# srd-05vdc-sl-c_single.net
KiCad netlist of a schematic drawn in EAGLE
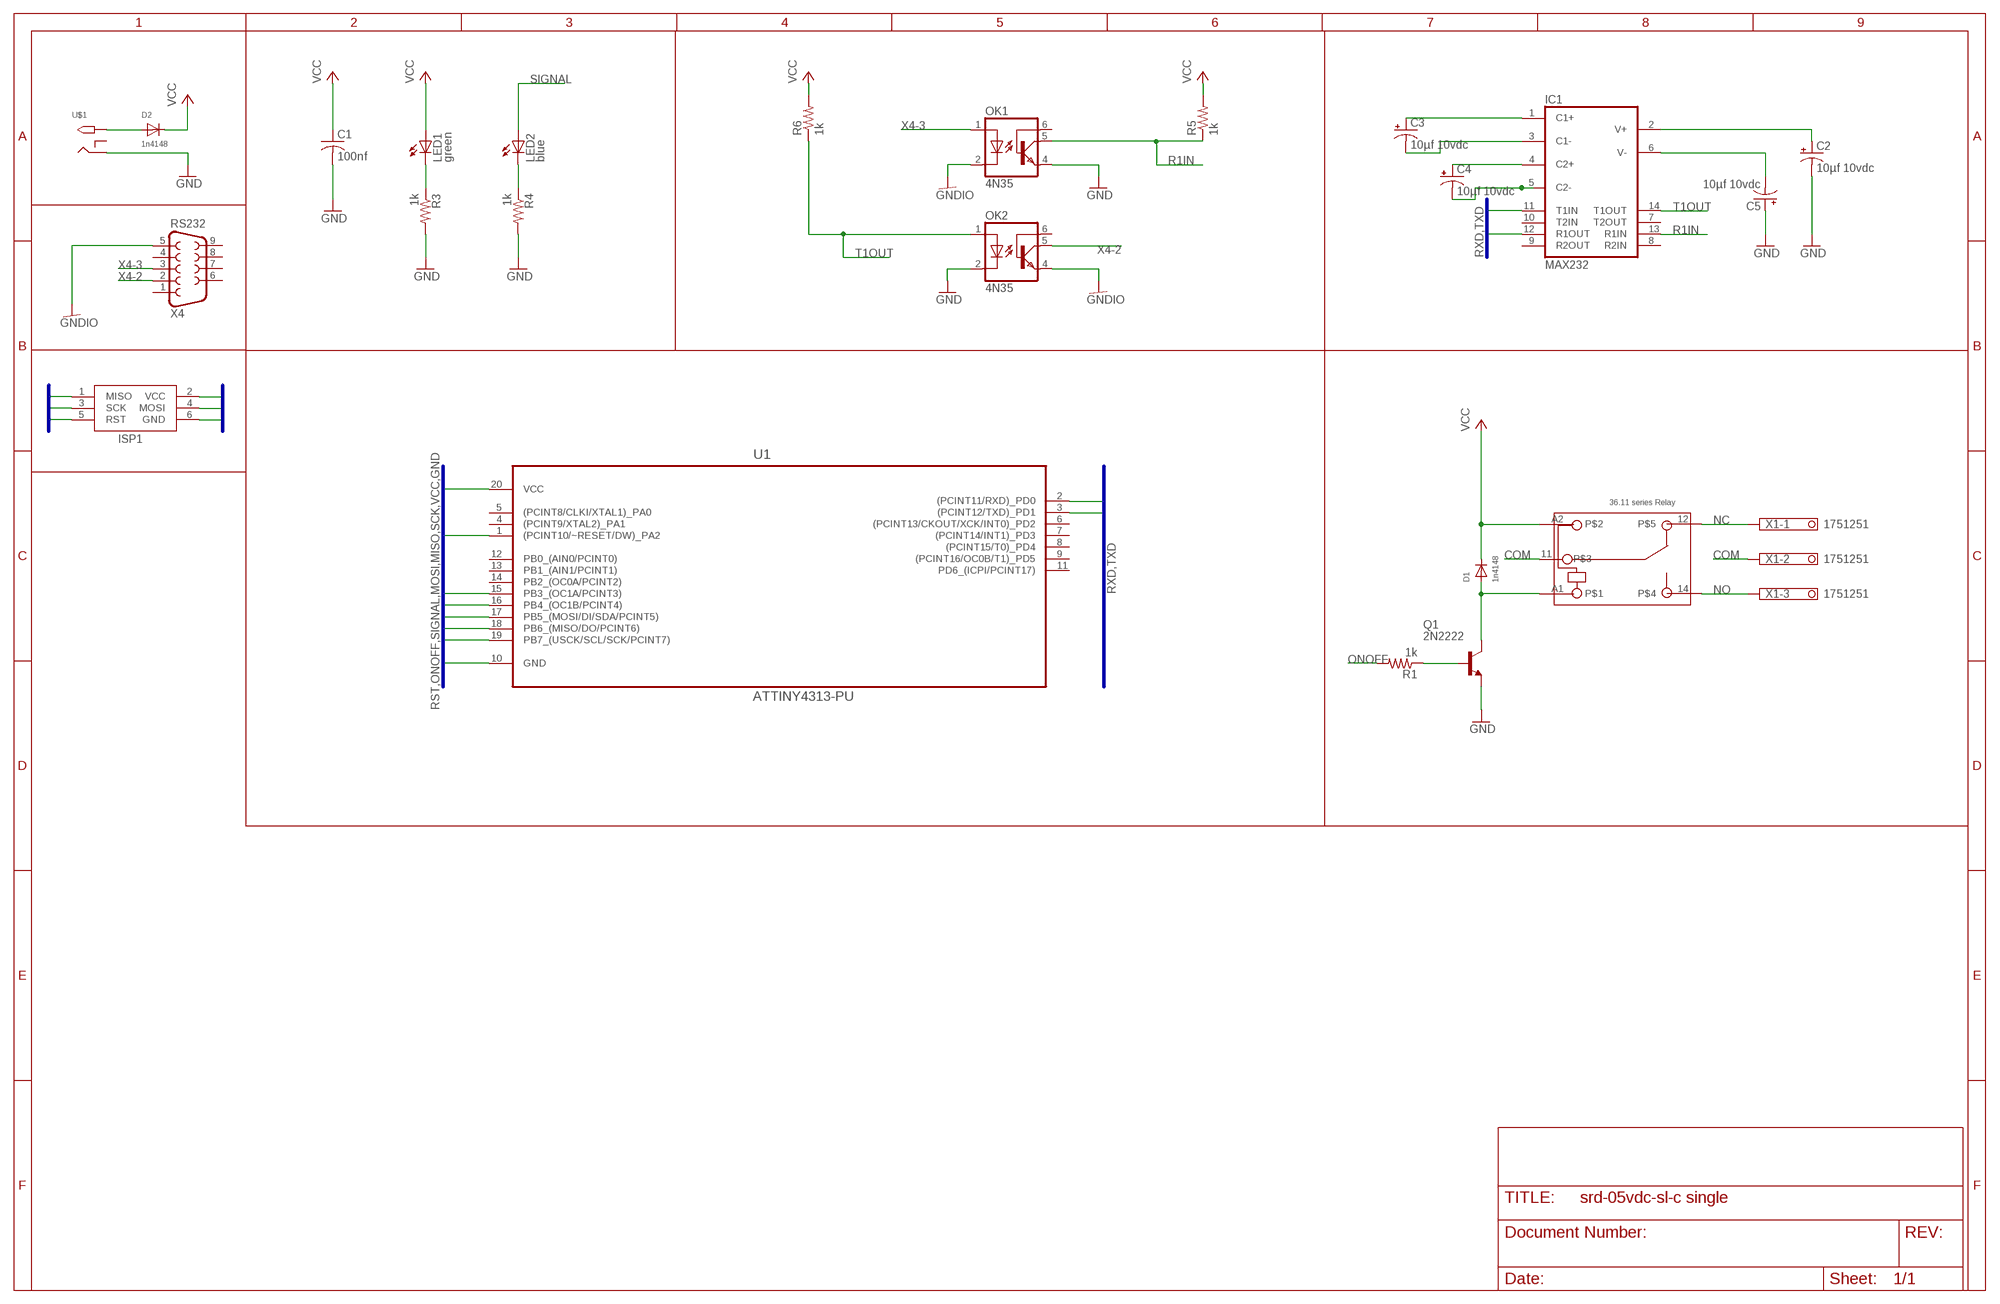
[diagram p0: schematic, sheet 1]

(export (version "E")
  (design (tool "Eeschema 10.0.6"))
  (components
    (comp (ref "C1")
      (value "100nf")
      (footprint "eagle-import:C025-025X050")
      (libsource (lib "eagle-import") (part "C-US025-025X050"))
    )
    (comp (ref "C2")
      (value "10µf 10vdc")
      (footprint "eagle-import:E2,5-6")
      (libsource (lib "eagle-import") (part "CPOL-USE2.5-6"))
    )
    (comp (ref "C3")
      (value "10µf 10vdc")
      (footprint "eagle-import:E2,5-6")
      (libsource (lib "eagle-import") (part "CPOL-USE2.5-6"))
    )
    (comp (ref "C4")
      (value "10µf 10vdc")
      (footprint "eagle-import:E2,5-6")
      (libsource (lib "eagle-import") (part "CPOL-USE2.5-6"))
    )
    (comp (ref "C5")
      (value "10µf 10vdc")
      (footprint "eagle-import:E2,5-6")
      (libsource (lib "eagle-import") (part "CPOL-USE2.5-6"))
    )
    (comp (ref "D1")
      (value "1n4148")
      (footprint "eagle-import:DO-1N4148")
      (libsource (lib "eagle-import") (part "DIODEDO-1N4148"))
    )
    (comp (ref "D2")
      (value "1n4148")
      (footprint "eagle-import:DO-1N4148")
      (libsource (lib "eagle-import") (part "DIODEDO-1N4148"))
    )
    (comp (ref "IC1")
      (value "MAX232")
      (footprint "eagle-import:DIL16")
      (fields (field (name "MF") "MAXIM") (field (name "MPN") "MAX232ACPE+"))
      (libsource (lib "eagle-import") (part "MAX232"))
    )
    (comp (ref "ISP1")
      (value "AVRISP-6")
      (footprint "eagle-import:AVRISP")
      (libsource (lib "eagle-import") (part "AVRISP-6"))
    )
    (comp (ref "LED1")
      (value "green")
      (footprint "eagle-import:LED3MM")
      (libsource (lib "eagle-import") (part "LED3MM"))
    )
    (comp (ref "LED2")
      (value "blue")
      (footprint "eagle-import:LED3MM")
      (libsource (lib "eagle-import") (part "LED3MM"))
    )
    (comp (ref "OK1")
      (value "4N35")
      (footprint "eagle-import:DIL06")
      (fields (field (name "MF") "FAIRCHILD SEMICONDUCTOR"))
      (libsource (lib "eagle-import") (part "4N35"))
    )
    (comp (ref "OK2")
      (value "4N35")
      (footprint "eagle-import:DIL06")
      (fields (field (name "MF") "FAIRCHILD SEMICONDUCTOR"))
      (libsource (lib "eagle-import") (part "4N35"))
    )
    (comp (ref "Q1")
      (value "2N2222")
      (footprint "eagle-import:TO92-EBC-OVAL")
      (libsource (lib "eagle-import") (part "2N2222"))
    )
    (comp (ref "R1")
      (value "1k")
      (footprint "eagle-import:0204_7")
      (libsource (lib "eagle-import") (part "R-US_0204/7"))
    )
    (comp (ref "R3")
      (value "1k")
      (footprint "eagle-import:0204_7")
      (libsource (lib "eagle-import") (part "R-US_0204/7"))
    )
    (comp (ref "R4")
      (value "1k")
      (footprint "eagle-import:0204_7")
      (libsource (lib "eagle-import") (part "R-US_0204/7"))
    )
    (comp (ref "R5")
      (value "1k")
      (footprint "eagle-import:0204_7")
      (libsource (lib "eagle-import") (part "R-US_0204/7"))
    )
    (comp (ref "R6")
      (value "1k")
      (footprint "eagle-import:0204_7")
      (libsource (lib "eagle-import") (part "R-US_0204/7"))
    )
    (comp (ref "SRD-05VDC-SL-C")
      (value "36.11")
      (footprint "eagle-import:36.11")
      (libsource (lib "eagle-import") (part "36.11"))
    )
    (comp (ref "U$1")
      (value "2.1MMJACKTHM")
      (footprint "eagle-import:PJ-102A")
      (libsource (lib "eagle-import") (part "2.1MMJACKTHM"))
    )
    (comp (ref "U1")
      (value "ATTINY4313-PU")
      (footprint "eagle-import:DIP254P762X533-20")
      (libsource (lib "eagle-import") (part "ATTINY4313-PU"))
    )
    (comp (ref "X1")
      (value "1751251")
      (footprint "eagle-import:1751251")
      (libsource (lib "eagle-import") (part "1751251"))
    )
    (comp (ref "X4")
      (value "RS232")
      (footprint "eagle-import:F09H")
      (libsource (lib "eagle-import") (part "F09H"))
    )
  )
  (nets
    (net (code "1") (name "/COM") (class "Default")
      (node (ref "SRD-05VDC-SL-C") (pin "11") (pinfunction "P$3_11") (pintype "passive"))
      (node (ref "X1") (pin "2") (pinfunction "K_2") (pintype "passive"))
    )
    (net (code "2") (name "/MISO") (class "Default")
      (node (ref "ISP1") (pin "1") (pinfunction "MISO_1") (pintype "input"))
      (node (ref "U1") (pin "18") (pinfunction "PB6_(MISO/DO/PCINT6)_18") (pintype "bidirectional"))
    )
    (net (code "3") (name "/MOSI") (class "Default")
      (node (ref "ISP1") (pin "4") (pinfunction "MOSI_4") (pintype "output"))
      (node (ref "U1") (pin "17") (pinfunction "PB5_(MOSI/DI/SDA/PCINT5)_17") (pintype "bidirectional"))
    )
    (net (code "4") (name "/NC") (class "Default")
      (node (ref "SRD-05VDC-SL-C") (pin "12") (pinfunction "P$5_12") (pintype "passive"))
      (node (ref "X1") (pin "1") (pinfunction "K_1") (pintype "passive"))
    )
    (net (code "5") (name "/NO") (class "Default")
      (node (ref "SRD-05VDC-SL-C") (pin "14") (pinfunction "P$4_14") (pintype "passive"))
      (node (ref "X1") (pin "3") (pinfunction "K_3") (pintype "passive"))
    )
    (net (code "6") (name "/ONOFF") (class "Default")
      (node (ref "R1") (pin "2") (pinfunction "2_2") (pintype "passive"))
      (node (ref "U1") (pin "15") (pinfunction "PB3_(OC1A/PCINT3)_15") (pintype "power_in"))
    )
    (net (code "7") (name "/R1IN") (class "Default")
      (node (ref "IC1") (pin "13") (pinfunction "R1IN_13") (pintype "input"))
      (node (ref "OK1") (pin "5") (pinfunction "COL_5") (pintype "passive"))
      (node (ref "R5") (pin "1") (pinfunction "1_1") (pintype "passive"))
    )
    (net (code "8") (name "/RST") (class "Default")
      (node (ref "ISP1") (pin "5") (pinfunction "RST_5") (pintype "output"))
      (node (ref "U1") (pin "1") (pinfunction "(PCINT10/~{RESET/DW})_PA2_1") (pintype "bidirectional"))
    )
    (net (code "9") (name "/RXD") (class "Default")
      (node (ref "IC1") (pin "12") (pinfunction "R1OUT_12") (pintype "output"))
      (node (ref "U1") (pin "2") (pinfunction "(PCINT11/RXD)_PD0_2") (pintype "bidirectional"))
    )
    (net (code "10") (name "/SCK") (class "Default")
      (node (ref "ISP1") (pin "3") (pinfunction "SCK_3") (pintype "output"))
      (node (ref "U1") (pin "19") (pinfunction "PB7_(USCK/SCL/SCK/PCINT7)_19") (pintype "bidirectional"))
    )
    (net (code "11") (name "/SIGNAL") (class "Default")
      (node (ref "LED2") (pin "A") (pinfunction "A_A") (pintype "passive"))
      (node (ref "U1") (pin "16") (pinfunction "PB4_(OC1B/PCINT4)_16") (pintype "passive"))
    )
    (net (code "12") (name "/T1OUT") (class "Default")
      (node (ref "IC1") (pin "14") (pinfunction "T1OUT_14") (pintype "output"))
      (node (ref "OK2") (pin "1") (pinfunction "A_1") (pintype "passive"))
      (node (ref "R6") (pin "1") (pinfunction "1_1") (pintype "passive"))
    )
    (net (code "13") (name "/TXD") (class "Default")
      (node (ref "IC1") (pin "11") (pinfunction "T1IN_11") (pintype "input"))
      (node (ref "U1") (pin "3") (pinfunction "(PCINT12/TXD)_PD1_3") (pintype "bidirectional"))
    )
    (net (code "14") (name "/X4-2") (class "Default")
      (node (ref "OK2") (pin "5") (pinfunction "COL_5") (pintype "passive"))
      (node (ref "X4") (pin "2") (pinfunction "2_2") (pintype "passive"))
    )
    (net (code "15") (name "/X4-3") (class "Default")
      (node (ref "OK1") (pin "1") (pinfunction "A_1") (pintype "passive"))
      (node (ref "X4") (pin "3") (pinfunction "3_3") (pintype "passive"))
    )
    (net (code "18") (name "GND") (class "Default")
      (node (ref "C1") (pin "2") (pinfunction "2_2") (pintype "passive"))
      (node (ref "C2") (pin "-") (pinfunction "-_-") (pintype "passive"))
      (node (ref "C5") (pin "+") (pinfunction "+_+") (pintype "passive"))
      (node (ref "ISP1") (pin "6") (pinfunction "GND_6") (pintype "power_in"))
      (node (ref "OK1") (pin "4") (pinfunction "EMI_4") (pintype "passive"))
      (node (ref "OK2") (pin "2") (pinfunction "C_2") (pintype "passive"))
      (node (ref "Q1") (pin "E") (pinfunction "E_E") (pintype "passive"))
      (node (ref "R3") (pin "2") (pinfunction "2_2") (pintype "passive"))
      (node (ref "R4") (pin "2") (pinfunction "2_2") (pintype "passive"))
      (node (ref "U$1") (pin "RING") (pinfunction "RING_RING") (pintype "bidirectional"))
      (node (ref "U1") (pin "10") (pinfunction "GND_10") (pintype "passive"))
    )
    (net (code "19") (name "GNDIO") (class "Default")
      (node (ref "OK1") (pin "2") (pinfunction "C_2") (pintype "passive"))
      (node (ref "OK2") (pin "4") (pinfunction "EMI_4") (pintype "passive"))
      (node (ref "X4") (pin "5") (pinfunction "5_5") (pintype "passive"))
    )
    (net (code "20") (name "Net-(D2-PadA)") (class "Default")
      (node (ref "D2") (pin "A") (pinfunction "A_A") (pintype "passive"))
      (node (ref "U$1") (pin "TIP") (pinfunction "TIP_TIP") (pintype "bidirectional"))
    )
    (net (code "21") (name "Net-(IC1A-C1+)") (class "Default")
      (node (ref "C3") (pin "+") (pinfunction "+_+") (pintype "passive"))
      (node (ref "IC1") (pin "1") (pinfunction "C1+_1") (pintype "bidirectional"))
    )
    (net (code "22") (name "Net-(IC1A-C1-)") (class "Default")
      (node (ref "C3") (pin "-") (pinfunction "-_-") (pintype "passive"))
      (node (ref "IC1") (pin "3") (pinfunction "C1-_3") (pintype "bidirectional"))
    )
    (net (code "23") (name "Net-(IC1A-C2+)") (class "Default")
      (node (ref "C4") (pin "+") (pinfunction "+_+") (pintype "passive"))
      (node (ref "IC1") (pin "4") (pinfunction "C2+_4") (pintype "bidirectional"))
    )
    (net (code "24") (name "Net-(IC1A-C2-)") (class "Default")
      (node (ref "C4") (pin "-") (pinfunction "-_-") (pintype "passive"))
      (node (ref "IC1") (pin "5") (pinfunction "C2-_5") (pintype "bidirectional"))
    )
    (net (code "25") (name "Net-(IC1A-V+)") (class "Default")
      (node (ref "C2") (pin "+") (pinfunction "+_+") (pintype "passive"))
      (node (ref "IC1") (pin "2") (pinfunction "V+_2") (pintype "bidirectional"))
    )
    (net (code "26") (name "Net-(IC1A-V-)") (class "Default")
      (node (ref "C5") (pin "-") (pinfunction "-_-") (pintype "passive"))
      (node (ref "IC1") (pin "6") (pinfunction "V-_6") (pintype "bidirectional"))
    )
    (net (code "27") (name "Net-(LED1-C)") (class "Default")
      (node (ref "LED1") (pin "K") (pinfunction "C_K") (pintype "passive"))
      (node (ref "R3") (pin "1") (pinfunction "1_1") (pintype "passive"))
    )
    (net (code "28") (name "Net-(LED2-C)") (class "Default")
      (node (ref "LED2") (pin "K") (pinfunction "C_K") (pintype "passive"))
      (node (ref "R4") (pin "1") (pinfunction "1_1") (pintype "passive"))
    )
    (net (code "29") (name "Net-(Q1-PadB)") (class "Default")
      (node (ref "Q1") (pin "B") (pinfunction "B_B") (pintype "passive"))
      (node (ref "R1") (pin "1") (pinfunction "1_1") (pintype "passive"))
    )
    (net (code "30") (name "Net-(SRD-05VDC-SL-C-P$1)") (class "Default")
      (node (ref "D1") (pin "A") (pinfunction "A_A") (pintype "passive"))
      (node (ref "Q1") (pin "C") (pinfunction "C_C") (pintype "passive"))
      (node (ref "SRD-05VDC-SL-C") (pin "A1") (pinfunction "P$1_A1") (pintype "passive"))
    )
    (net (code "31") (name "VCC") (class "Default")
      (node (ref "C1") (pin "1") (pinfunction "1_1") (pintype "passive"))
      (node (ref "D1") (pin "C") (pinfunction "C_C") (pintype "passive"))
      (node (ref "D2") (pin "C") (pinfunction "C_C") (pintype "passive"))
      (node (ref "ISP1") (pin "2") (pinfunction "VCC_2") (pintype "power_in"))
      (node (ref "LED1") (pin "A") (pinfunction "A_A") (pintype "passive"))
      (node (ref "R5") (pin "2") (pinfunction "2_2") (pintype "passive"))
      (node (ref "R6") (pin "2") (pinfunction "2_2") (pintype "passive"))
      (node (ref "SRD-05VDC-SL-C") (pin "A2") (pinfunction "P$2_A2") (pintype "passive"))
      (node (ref "U1") (pin "20") (pinfunction "VCC_20") (pintype "power_in"))
    )
    (net (code "32") (name "unconnected-(IC1A-R2IN-Pad8)") (class "Default")
      (node (ref "IC1") (pin "8") (pinfunction "R2IN_8") (pintype "input"))
    )
    (net (code "33") (name "unconnected-(IC1A-R2OUT-Pad9)") (class "Default")
      (node (ref "IC1") (pin "9") (pinfunction "R2OUT_9") (pintype "output"))
    )
    (net (code "34") (name "unconnected-(IC1A-T2IN-Pad10)") (class "Default")
      (node (ref "IC1") (pin "10") (pinfunction "T2IN_10") (pintype "input"))
    )
    (net (code "35") (name "unconnected-(IC1A-T2OUT-Pad7)") (class "Default")
      (node (ref "IC1") (pin "7") (pinfunction "T2OUT_7") (pintype "output"))
    )
    (net (code "36") (name "unconnected-(OK1-BAS-Pad6)") (class "Default")
      (node (ref "OK1") (pin "6") (pinfunction "BAS_6") (pintype "passive"))
    )
    (net (code "37") (name "unconnected-(OK2-BAS-Pad6)") (class "Default")
      (node (ref "OK2") (pin "6") (pinfunction "BAS_6") (pintype "passive"))
    )
    (net (code "38") (name "unconnected-(U$1-PadRING_SW)") (class "Default")
      (node (ref "U$1") (pin "RING_SW") (pinfunction "RING_SW_RING_SW") (pintype "bidirectional"))
    )
    (net (code "39") (name "unconnected-(U1-(PCINT8{slash}CLKI{slash}XTAL1)_PA0-Pad5)") (class "Default")
      (node (ref "U1") (pin "5") (pinfunction "(PCINT8/CLKI/XTAL1)_PA0_5") (pintype "bidirectional"))
    )
    (net (code "40") (name "unconnected-(U1-(PCINT9{slash}XTAL2)_PA1-Pad4)") (class "Default")
      (node (ref "U1") (pin "4") (pinfunction "(PCINT9/XTAL2)_PA1_4") (pintype "bidirectional"))
    )
    (net (code "41") (name "unconnected-(U1-(PCINT13{slash}CKOUT{slash}XCK{slash}INT0)_PD2-Pad6)") (class "Default")
      (node (ref "U1") (pin "6") (pinfunction "(PCINT13/CKOUT/XCK/INT0)_PD2_6") (pintype "bidirectional"))
    )
    (net (code "42") (name "unconnected-(U1-(PCINT14{slash}INT1)_PD3-Pad7)") (class "Default")
      (node (ref "U1") (pin "7") (pinfunction "(PCINT14/INT1)_PD3_7") (pintype "bidirectional"))
    )
    (net (code "43") (name "unconnected-(U1-(PCINT15{slash}T0)_PD4-Pad8)") (class "Default")
      (node (ref "U1") (pin "8") (pinfunction "(PCINT15/T0)_PD4_8") (pintype "bidirectional"))
    )
    (net (code "44") (name "unconnected-(U1-(PCINT16{slash}OC0B{slash}T1)_PD5-Pad9)") (class "Default")
      (node (ref "U1") (pin "9") (pinfunction "(PCINT16/OC0B/T1)_PD5_9") (pintype "bidirectional"))
    )
    (net (code "45") (name "unconnected-(U1-PB0_(AIN0{slash}PCINT0)-Pad12)") (class "Default")
      (node (ref "U1") (pin "12") (pinfunction "PB0_(AIN0/PCINT0)_12") (pintype "bidirectional"))
    )
    (net (code "46") (name "unconnected-(U1-PB1_(AIN1{slash}PCINT1)-Pad13)") (class "Default")
      (node (ref "U1") (pin "13") (pinfunction "PB1_(AIN1/PCINT1)_13") (pintype "bidirectional"))
    )
    (net (code "47") (name "unconnected-(U1-PB2_(OC0A{slash}PCINT2)-Pad14)") (class "Default")
      (node (ref "U1") (pin "14") (pinfunction "PB2_(OC0A/PCINT2)_14") (pintype "bidirectional"))
    )
    (net (code "48") (name "unconnected-(U1-PD6_(ICPI{slash}PCINT17)-Pad11)") (class "Default")
      (node (ref "U1") (pin "11") (pinfunction "PD6_(ICPI/PCINT17)_11") (pintype "bidirectional"))
    )
    (net (code "49") (name "unconnected-(X4-Pad1)") (class "Default")
      (node (ref "X4") (pin "1") (pinfunction "1_1") (pintype "passive"))
    )
    (net (code "50") (name "unconnected-(X4-Pad4)") (class "Default")
      (node (ref "X4") (pin "4") (pinfunction "4_4") (pintype "passive"))
    )
    (net (code "51") (name "unconnected-(X4-Pad6)") (class "Default")
      (node (ref "X4") (pin "6") (pinfunction "6_6") (pintype "passive"))
    )
    (net (code "52") (name "unconnected-(X4-Pad7)") (class "Default")
      (node (ref "X4") (pin "7") (pinfunction "7_7") (pintype "passive"))
    )
    (net (code "53") (name "unconnected-(X4-Pad8)") (class "Default")
      (node (ref "X4") (pin "8") (pinfunction "8_8") (pintype "passive"))
    )
    (net (code "54") (name "unconnected-(X4-Pad9)") (class "Default")
      (node (ref "X4") (pin "9") (pinfunction "9_9") (pintype "passive"))
    )
  )
)
